# MCU.net
KiCad netlist of a schematic drawn in Altium Designer
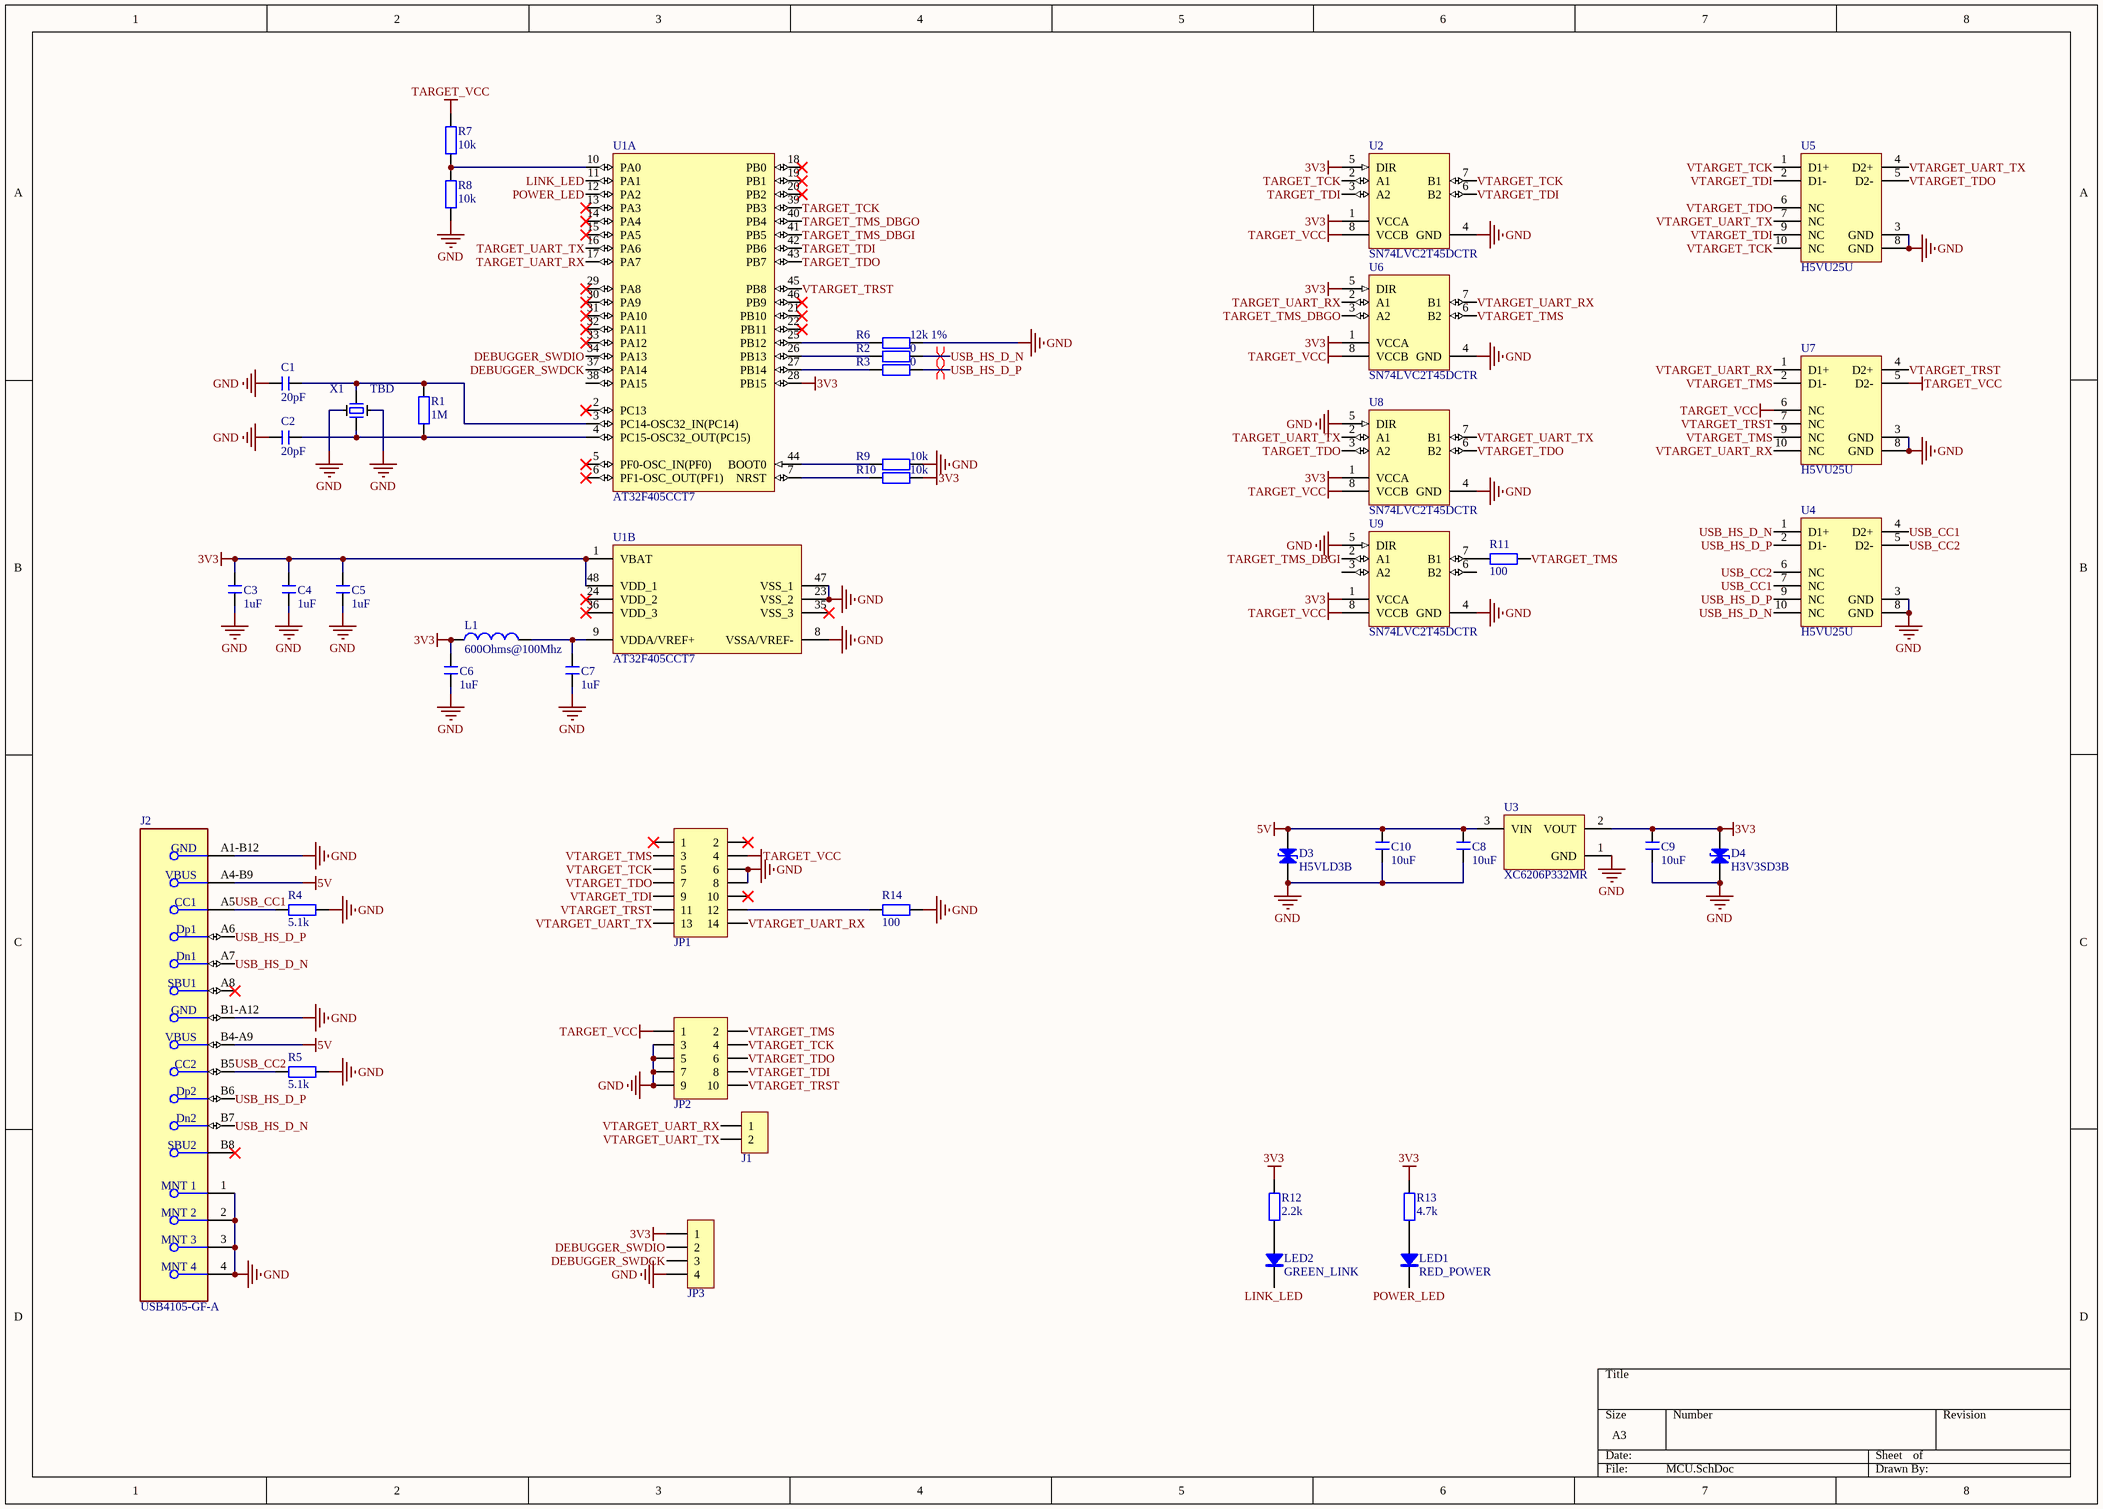
[diagram p0: MCU.SchDoc]

(export (version "E")
  (design (tool "Eeschema 10.0.6"))
  (components
    (comp (ref "C1") (value "20pF") (footprint "C0402") (libsource (lib "Passive") (part "C")))
    (comp (ref "C2") (value "20pF") (footprint "C0402") (libsource (lib "Passive") (part "C")))
    (comp (ref "C3") (value "1uF") (footprint "C0402") (libsource (lib "Passive") (part "C")))
    (comp (ref "C4") (value "1uF") (footprint "C0402") (libsource (lib "Passive") (part "C")))
    (comp (ref "C5") (value "1uF") (footprint "C0402") (libsource (lib "Passive") (part "C")))
    (comp (ref "C6") (value "1uF") (footprint "C0402") (libsource (lib "Passive") (part "C")))
    (comp (ref "C7") (value "1uF") (footprint "C0402") (libsource (lib "Passive") (part "C")))
    (comp (ref "C8") (value "10uF") (footprint "C0603") (libsource (lib "Passive") (part "C")))
    (comp (ref "C9") (value "10uF") (footprint "C0603") (libsource (lib "Passive") (part "C")))
    (comp (ref "C10") (value "10uF") (footprint "C0603") (libsource (lib "Passive") (part "C")))
    (comp (ref "D3")
      (value "H5VLD3B")
      (footprint "SOD-323")
      (description "瞬态电压抑制二极管")
      (fields (field (name "版权归属") "源创客"))
      (libsource (lib "Diode") (part "Generic_BiTVS"))
    )
    (comp (ref "D4")
      (value "H3V3SD3B")
      (footprint "SOD-323")
      (description "瞬态电压抑制二极管")
      (fields (field (name "版权归属") "源创客"))
      (libsource (lib "Diode") (part "Generic_BiTVS"))
    )
    (comp (ref "J1")
      (value "HDR-1X2")
      (footprint "HDR2.54-LI-2P")
      (fields (field (name "版权归属") "源创客"))
      (libsource (lib "Pin2.54") (part "Header 2"))
    )
    (comp (ref "J2")
      (value "USB4105-GF-A")
      (footprint "FP-USB4105-GF-A-MFG")
      (description "CONN RCPT USB2.0 TYPEC 5A")
      (fields
        (field (name "MANUFACTURER") "GCT")
        (field (name "OCTOPART") "https://octopart.com/usb4105-gf-a-gct-106627878")
      )
      (libsource (lib "Altium Content Vault") (part "e7c17a616881a82b79941196b4bec10"))
    )
    (comp (ref "JP1")
      (value "Header 2X7")
      (footprint "HDR1.27-LI-2x7P")
      (description "7*2P接插件")
      (fields (field (name "版权归属") "源创客"))
      (libsource (lib "Pin1.27") (part "Header 7X2"))
    )
    (comp (ref "JP2")
      (value "Header 5X2")
      (footprint "HDR2.54-LI-2x5P")
      (description "5*2P接插件")
      (fields (field (name "版权归属") "源创客"))
      (libsource (lib "Pin2.54") (part "Header 5X2"))
    )
    (comp (ref "JP3")
      (value "HDR-1X4")
      (footprint "HDR2.54-WS-4P")
      (description "4P接插件")
      (fields (field (name "版权归属") "源创客"))
      (libsource (lib "Pin2.54") (part "Header 4"))
    )
    (comp (ref "L1") (value "600Ohms@100Mhz") (footprint "L 0603_L") (libsource (lib "Passive") (part "L")))
    (comp (ref "LED1") (value "RED_POWER") (footprint "LED 0603R") (libsource (lib "Passive") (part "D")))
    (comp (ref "LED2") (value "GREEN_LINK") (footprint "LED 0603G") (libsource (lib "Passive") (part "D")))
    (comp (ref "R1") (value "1M") (footprint "R0402") (libsource (lib "Passive") (part "R")))
    (comp (ref "R2") (value "0") (footprint "R0402") (libsource (lib "Passive") (part "R")))
    (comp (ref "R3") (value "0") (footprint "R0402") (libsource (lib "Passive") (part "R")))
    (comp (ref "R4") (value "5.1k") (footprint "R0402") (libsource (lib "Passive") (part "R")))
    (comp (ref "R5") (value "5.1k") (footprint "R0402") (libsource (lib "Passive") (part "R")))
    (comp (ref "R6") (value "12k 1%") (footprint "R0402") (libsource (lib "Passive") (part "R")))
    (comp (ref "R7") (value "10k") (footprint "R0402") (libsource (lib "Passive") (part "R")))
    (comp (ref "R8") (value "10k") (footprint "R0402") (libsource (lib "Passive") (part "R")))
    (comp (ref "R9") (value "10k") (footprint "R0402") (libsource (lib "Passive") (part "R")))
    (comp (ref "R10") (value "10k") (footprint "R0402") (libsource (lib "Passive") (part "R")))
    (comp (ref "R11") (value "100") (footprint "R0402") (libsource (lib "Passive") (part "R")))
    (comp (ref "R12") (value "2.2k") (footprint "R0402") (libsource (lib "Passive") (part "R")))
    (comp (ref "R13") (value "4.7k") (footprint "R0402") (libsource (lib "Passive") (part "R")))
    (comp (ref "R14") (value "100") (footprint "R0402") (libsource (lib "Passive") (part "R")))
    (comp (ref "U1")
      (value "AT32F405CCT7")
      (footprint "STM-LQFP48_N")
      (fields (field (name "PARTNUMBER") "STM32F303CBT6"))
      (libsource (lib "Altium Content Vault") (part "MC-ARM-STM32F303-SQ48"))
    )
    (comp (ref "U2")
      (value "SN74LVC2T45DCTR")
      (footprint "DCT0008A_N")
      (fields
        (field (name "MANUFACTURER") "Texas Instruments")
        (field (name "GENERIC PART NUMBER") "SN74LVC2T45")
      )
      (libsource (lib "Altium Content Vault") (part "TI-SN74XVC2T45-8"))
    )
    (comp (ref "U3")
      (value "XC6206P332MR")
      (footprint "SOT-23-TT3_N")
      (description "Low Quiescent Current LDO, 3-Pin SOT-23, Extended Temperature, Tape and Reel")
      (libsource (lib "Altium Content Vault") (part "PM-LINEREG-MCP1700-IL3"))
    )
    (comp (ref "U4")
      (value "H5VU25U")
      (footprint "DQA0010A_V")
      (fields (field (name "PARTNUMBER") "TPD4EUSB30DQAR") (field (name "MANUFACTURER") "Texas Instruments"))
      (libsource (lib "Altium Content Vault") (part "TI-TPD4EUSB30-SON_DQA-10"))
    )
    (comp (ref "U5")
      (value "H5VU25U")
      (footprint "DQA0010A_V")
      (fields (field (name "PARTNUMBER") "TPD4EUSB30DQAR") (field (name "MANUFACTURER") "Texas Instruments"))
      (libsource (lib "Altium Content Vault") (part "TI-TPD4EUSB30-SON_DQA-10"))
    )
    (comp (ref "U6")
      (value "SN74LVC2T45DCTR")
      (footprint "DCT0008A_N")
      (fields
        (field (name "MANUFACTURER") "Texas Instruments")
        (field (name "GENERIC PART NUMBER") "SN74LVC2T45")
      )
      (libsource (lib "Altium Content Vault") (part "TI-SN74XVC2T45-8"))
    )
    (comp (ref "U7")
      (value "H5VU25U")
      (footprint "DQA0010A_V")
      (fields (field (name "PARTNUMBER") "TPD4EUSB30DQAR") (field (name "MANUFACTURER") "Texas Instruments"))
      (libsource (lib "Altium Content Vault") (part "TI-TPD4EUSB30-SON_DQA-10"))
    )
    (comp (ref "U8")
      (value "SN74LVC2T45DCTR")
      (footprint "DCT0008A_N")
      (fields
        (field (name "MANUFACTURER") "Texas Instruments")
        (field (name "GENERIC PART NUMBER") "SN74LVC2T45")
      )
      (libsource (lib "Altium Content Vault") (part "TI-SN74XVC2T45-8"))
    )
    (comp (ref "U9")
      (value "SN74LVC2T45DCTR")
      (footprint "DCT0008A_N")
      (fields
        (field (name "MANUFACTURER") "Texas Instruments")
        (field (name "GENERIC PART NUMBER") "SN74LVC2T45")
      )
      (libsource (lib "Altium Content Vault") (part "TI-SN74XVC2T45-8"))
    )
    (comp (ref "X1") (value "TBD") (footprint "3225") (libsource (lib "Passive") (part "X")))
  )
  (nets
    (net (code "1") (name "/DEBUGGER_SWDCK") (class "Default")
      (node (ref "JP3") (pin "3") (pinfunction "3_3") (pintype "passive"))
      (node (ref "U1") (pin "37") (pinfunction "PA14_37") (pintype "bidirectional"))
    )
    (net (code "2") (name "/DEBUGGER_SWDIO") (class "Default")
      (node (ref "JP3") (pin "2") (pinfunction "2_2") (pintype "passive"))
      (node (ref "U1") (pin "34") (pinfunction "PA13_34") (pintype "bidirectional"))
    )
    (net (code "3") (name "/LINK_LED") (class "Default")
      (node (ref "LED2") (pin "2") (pinfunction "K_2") (pintype "passive"))
      (node (ref "U1") (pin "11") (pinfunction "PA1_11") (pintype "bidirectional"))
    )
    (net (code "4") (name "/POWER_LED") (class "Default")
      (node (ref "LED1") (pin "2") (pinfunction "K_2") (pintype "passive"))
      (node (ref "U1") (pin "12") (pinfunction "PA2_12") (pintype "bidirectional"))
    )
    (net (code "5") (name "/TARGET_TCK") (class "Default")
      (node (ref "U1") (pin "39") (pinfunction "PB3_39") (pintype "bidirectional"))
      (node (ref "U2") (pin "2") (pinfunction "A1_2") (pintype "bidirectional"))
    )
    (net (code "6") (name "/TARGET_TDI") (class "Default")
      (node (ref "U1") (pin "42") (pinfunction "PB6_42") (pintype "bidirectional"))
      (node (ref "U2") (pin "3") (pinfunction "A2_3") (pintype "bidirectional"))
    )
    (net (code "7") (name "/TARGET_TDO") (class "Default")
      (node (ref "U1") (pin "43") (pinfunction "PB7_43") (pintype "bidirectional"))
      (node (ref "U8") (pin "3") (pinfunction "A2_3") (pintype "bidirectional"))
    )
    (net (code "8") (name "/TARGET_TMS_DBGI") (class "Default")
      (node (ref "U1") (pin "41") (pinfunction "PB5_41") (pintype "bidirectional"))
      (node (ref "U9") (pin "2") (pinfunction "A1_2") (pintype "bidirectional"))
    )
    (net (code "9") (name "/TARGET_TMS_DBGO") (class "Default")
      (node (ref "U1") (pin "40") (pinfunction "PB4_40") (pintype "bidirectional"))
      (node (ref "U6") (pin "3") (pinfunction "A2_3") (pintype "bidirectional"))
    )
    (net (code "10") (name "/TARGET_UART_RX") (class "Default")
      (node (ref "U1") (pin "17") (pinfunction "PA7_17") (pintype "bidirectional"))
      (node (ref "U6") (pin "2") (pinfunction "A1_2") (pintype "bidirectional"))
    )
    (net (code "11") (name "/TARGET_UART_TX") (class "Default")
      (node (ref "U1") (pin "16") (pinfunction "PA6_16") (pintype "bidirectional"))
      (node (ref "U8") (pin "2") (pinfunction "A1_2") (pintype "bidirectional"))
    )
    (net (code "12") (name "/USB_CC1") (class "Default")
      (node (ref "J2") (pin "A5") (pinfunction "CC1_A5") (pintype "power_in"))
      (node (ref "R4") (pin "2") (pinfunction "2_2") (pintype "passive"))
      (node (ref "U4") (pin "4") (pinfunction "D2+_4") (pintype "passive"))
      (node (ref "U4") (pin "7") (pinfunction "NC_7") (pintype "passive"))
    )
    (net (code "13") (name "/USB_CC2") (class "Default")
      (node (ref "J2") (pin "B5") (pinfunction "CC2_B5") (pintype "bidirectional"))
      (node (ref "R5") (pin "2") (pinfunction "2_2") (pintype "passive"))
      (node (ref "U4") (pin "5") (pinfunction "D2-_5") (pintype "passive"))
      (node (ref "U4") (pin "6") (pinfunction "NC_6") (pintype "passive"))
    )
    (net (code "14") (name "/USB_HS_D_N") (class "Default")
      (node (ref "J2") (pin "A7") (pinfunction "Dn1_A7") (pintype "bidirectional"))
      (node (ref "J2") (pin "B7") (pinfunction "Dn2_B7") (pintype "bidirectional"))
      (node (ref "R2") (pin "1") (pinfunction "1_1") (pintype "passive"))
      (node (ref "U4") (pin "1") (pinfunction "D1+_1") (pintype "passive"))
      (node (ref "U4") (pin "10") (pinfunction "NC_10") (pintype "passive"))
    )
    (net (code "15") (name "/USB_HS_D_P") (class "Default")
      (node (ref "J2") (pin "A6") (pinfunction "Dp1_A6") (pintype "bidirectional"))
      (node (ref "J2") (pin "B6") (pinfunction "Dp2_B6") (pintype "bidirectional"))
      (node (ref "R3") (pin "1") (pinfunction "1_1") (pintype "passive"))
      (node (ref "U4") (pin "2") (pinfunction "D1-_2") (pintype "passive"))
      (node (ref "U4") (pin "9") (pinfunction "NC_9") (pintype "passive"))
    )
    (net (code "16") (name "/VTARGET_TCK") (class "Default")
      (node (ref "JP1") (pin "5") (pinfunction "5_5") (pintype "passive"))
      (node (ref "JP2") (pin "4") (pinfunction "4_4") (pintype "passive"))
      (node (ref "U2") (pin "7") (pinfunction "B1_7") (pintype "bidirectional"))
      (node (ref "U5") (pin "1") (pinfunction "D1+_1") (pintype "passive"))
      (node (ref "U5") (pin "10") (pinfunction "NC_10") (pintype "passive"))
    )
    (net (code "17") (name "/VTARGET_TDI") (class "Default")
      (node (ref "JP1") (pin "9") (pinfunction "9_9") (pintype "passive"))
      (node (ref "JP2") (pin "8") (pinfunction "8_8") (pintype "passive"))
      (node (ref "U2") (pin "6") (pinfunction "B2_6") (pintype "bidirectional"))
      (node (ref "U5") (pin "2") (pinfunction "D1-_2") (pintype "passive"))
      (node (ref "U5") (pin "9") (pinfunction "NC_9") (pintype "passive"))
    )
    (net (code "18") (name "/VTARGET_TDO") (class "Default")
      (node (ref "JP1") (pin "7") (pinfunction "7_7") (pintype "passive"))
      (node (ref "JP2") (pin "6") (pinfunction "6_6") (pintype "passive"))
      (node (ref "U5") (pin "5") (pinfunction "D2-_5") (pintype "passive"))
      (node (ref "U5") (pin "6") (pinfunction "NC_6") (pintype "passive"))
      (node (ref "U8") (pin "6") (pinfunction "B2_6") (pintype "bidirectional"))
    )
    (net (code "19") (name "/VTARGET_TMS") (class "Default")
      (node (ref "JP1") (pin "3") (pinfunction "3_3") (pintype "passive"))
      (node (ref "JP2") (pin "2") (pinfunction "2_2") (pintype "passive"))
      (node (ref "R11") (pin "1") (pinfunction "1_1") (pintype "passive"))
      (node (ref "U6") (pin "6") (pinfunction "B2_6") (pintype "bidirectional"))
      (node (ref "U7") (pin "2") (pinfunction "D1-_2") (pintype "passive"))
      (node (ref "U7") (pin "9") (pinfunction "NC_9") (pintype "passive"))
    )
    (net (code "20") (name "/VTARGET_TRST") (class "Default")
      (node (ref "JP1") (pin "11") (pinfunction "11_11") (pintype "passive"))
      (node (ref "JP2") (pin "10") (pinfunction "10_10") (pintype "passive"))
      (node (ref "U1") (pin "45") (pinfunction "PB8_45") (pintype "bidirectional"))
      (node (ref "U7") (pin "4") (pinfunction "D2+_4") (pintype "passive"))
      (node (ref "U7") (pin "7") (pinfunction "NC_7") (pintype "passive"))
    )
    (net (code "21") (name "/VTARGET_UART_RX") (class "Default")
      (node (ref "J1") (pin "1") (pinfunction "1_1") (pintype "passive"))
      (node (ref "JP1") (pin "14") (pinfunction "14_14") (pintype "passive"))
      (node (ref "U6") (pin "7") (pinfunction "B1_7") (pintype "bidirectional"))
      (node (ref "U7") (pin "1") (pinfunction "D1+_1") (pintype "passive"))
      (node (ref "U7") (pin "10") (pinfunction "NC_10") (pintype "passive"))
    )
    (net (code "22") (name "/VTARGET_UART_TX") (class "Default")
      (node (ref "J1") (pin "2") (pinfunction "2_2") (pintype "passive"))
      (node (ref "JP1") (pin "13") (pinfunction "13_13") (pintype "passive"))
      (node (ref "U5") (pin "4") (pinfunction "D2+_4") (pintype "passive"))
      (node (ref "U5") (pin "7") (pinfunction "NC_7") (pintype "passive"))
      (node (ref "U8") (pin "7") (pinfunction "B1_7") (pintype "bidirectional"))
    )
    (net (code "23") (name "3V3") (class "Default")
      (node (ref "C3") (pin "1") (pinfunction "1_1") (pintype "passive"))
      (node (ref "C4") (pin "1") (pinfunction "1_1") (pintype "passive"))
      (node (ref "C5") (pin "1") (pinfunction "1_1") (pintype "passive"))
      (node (ref "C6") (pin "1") (pinfunction "1_1") (pintype "passive"))
      (node (ref "C9") (pin "1") (pinfunction "1_1") (pintype "passive"))
      (node (ref "D4") (pin "1") (pinfunction "A_1") (pintype "passive"))
      (node (ref "JP3") (pin "1") (pinfunction "1_1") (pintype "passive"))
      (node (ref "L1") (pin "1") (pinfunction "1_1") (pintype "passive"))
      (node (ref "R10") (pin "1") (pinfunction "1_1") (pintype "passive"))
      (node (ref "R12") (pin "1") (pinfunction "1_1") (pintype "passive"))
      (node (ref "R13") (pin "1") (pinfunction "1_1") (pintype "passive"))
      (node (ref "U1") (pin "1") (pinfunction "VBAT_1") (pintype "power_in"))
      (node (ref "U1") (pin "28") (pinfunction "PB15_28") (pintype "bidirectional"))
      (node (ref "U1") (pin "48") (pinfunction "VDD_1_48") (pintype "power_in"))
      (node (ref "U2") (pin "1") (pinfunction "VCCA_1") (pintype "power_in"))
      (node (ref "U2") (pin "5") (pinfunction "DIR_5") (pintype "input"))
      (node (ref "U3") (pin "2") (pinfunction "VOUT_2") (pintype "power_in"))
      (node (ref "U6") (pin "1") (pinfunction "VCCA_1") (pintype "power_in"))
      (node (ref "U6") (pin "5") (pinfunction "DIR_5") (pintype "input"))
      (node (ref "U8") (pin "1") (pinfunction "VCCA_1") (pintype "power_in"))
      (node (ref "U9") (pin "1") (pinfunction "VCCA_1") (pintype "power_in"))
    )
    (net (code "24") (name "5V") (class "Default")
      (node (ref "C10") (pin "1") (pinfunction "1_1") (pintype "passive"))
      (node (ref "C8") (pin "1") (pinfunction "1_1") (pintype "passive"))
      (node (ref "D3") (pin "1") (pinfunction "A_1") (pintype "passive"))
      (node (ref "J2") (pin "A4-B9") (pinfunction "VBUS_A4-B9") (pintype "power_in"))
      (node (ref "J2") (pin "B4-A9") (pinfunction "VBUS_B4-A9") (pintype "bidirectional"))
      (node (ref "U3") (pin "3") (pinfunction "VIN_3") (pintype "power_in"))
    )
    (net (code "25") (name "GND") (class "Default")
      (node (ref "C1") (pin "2") (pinfunction "2_2") (pintype "passive"))
      (node (ref "C10") (pin "2") (pinfunction "2_2") (pintype "passive"))
      (node (ref "C2") (pin "2") (pinfunction "2_2") (pintype "passive"))
      (node (ref "C3") (pin "2") (pinfunction "2_2") (pintype "passive"))
      (node (ref "C4") (pin "2") (pinfunction "2_2") (pintype "passive"))
      (node (ref "C5") (pin "2") (pinfunction "2_2") (pintype "passive"))
      (node (ref "C6") (pin "2") (pinfunction "2_2") (pintype "passive"))
      (node (ref "C7") (pin "2") (pinfunction "2_2") (pintype "passive"))
      (node (ref "C8") (pin "2") (pinfunction "2_2") (pintype "passive"))
      (node (ref "C9") (pin "2") (pinfunction "2_2") (pintype "passive"))
      (node (ref "D3") (pin "2") (pinfunction "K_2") (pintype "passive"))
      (node (ref "D4") (pin "2") (pinfunction "K_2") (pintype "passive"))
      (node (ref "J2") (pin "1") (pinfunction "MNT_1_1") (pintype "power_in"))
      (node (ref "J2") (pin "2") (pinfunction "MNT_2_2") (pintype "power_in"))
      (node (ref "J2") (pin "3") (pinfunction "MNT_3_3") (pintype "power_in"))
      (node (ref "J2") (pin "4") (pinfunction "MNT_4_4") (pintype "power_in"))
      (node (ref "J2") (pin "A1-B12") (pinfunction "GND_A1-B12") (pintype "power_in"))
      (node (ref "J2") (pin "B1-A12") (pinfunction "GND_B1-A12") (pintype "bidirectional"))
      (node (ref "JP1") (pin "6") (pinfunction "6_6") (pintype "passive"))
      (node (ref "JP1") (pin "8") (pinfunction "8_8") (pintype "passive"))
      (node (ref "JP2") (pin "3") (pinfunction "3_3") (pintype "passive"))
      (node (ref "JP2") (pin "5") (pinfunction "5_5") (pintype "passive"))
      (node (ref "JP2") (pin "7") (pinfunction "7_7") (pintype "passive"))
      (node (ref "JP2") (pin "9") (pinfunction "9_9") (pintype "passive"))
      (node (ref "JP3") (pin "4") (pinfunction "4_4") (pintype "passive"))
      (node (ref "R14") (pin "1") (pinfunction "1_1") (pintype "passive"))
      (node (ref "R4") (pin "1") (pinfunction "1_1") (pintype "passive"))
      (node (ref "R5") (pin "1") (pinfunction "1_1") (pintype "passive"))
      (node (ref "R6") (pin "1") (pinfunction "1_1") (pintype "passive"))
      (node (ref "R8") (pin "1") (pinfunction "1_1") (pintype "passive"))
      (node (ref "R9") (pin "1") (pinfunction "1_1") (pintype "passive"))
      (node (ref "U1") (pin "23") (pinfunction "VSS_2_23") (pintype "power_in"))
      (node (ref "U1") (pin "47") (pinfunction "VSS_1_47") (pintype "power_in"))
      (node (ref "U1") (pin "8") (pinfunction "VSSA/VREF-_8") (pintype "power_in"))
      (node (ref "U2") (pin "4") (pinfunction "GND_4") (pintype "power_in"))
      (node (ref "U3") (pin "1") (pinfunction "GND_1") (pintype "power_in"))
      (node (ref "U4") (pin "3") (pinfunction "GND_3") (pintype "power_in"))
      (node (ref "U4") (pin "8") (pinfunction "GND_8") (pintype "power_in"))
      (node (ref "U5") (pin "3") (pinfunction "GND_3") (pintype "power_in"))
      (node (ref "U5") (pin "8") (pinfunction "GND_8") (pintype "power_in"))
      (node (ref "U6") (pin "4") (pinfunction "GND_4") (pintype "power_in"))
      (node (ref "U7") (pin "3") (pinfunction "GND_3") (pintype "power_in"))
      (node (ref "U7") (pin "8") (pinfunction "GND_8") (pintype "power_in"))
      (node (ref "U8") (pin "4") (pinfunction "GND_4") (pintype "power_in"))
      (node (ref "U8") (pin "5") (pinfunction "DIR_5") (pintype "input"))
      (node (ref "U9") (pin "4") (pinfunction "GND_4") (pintype "power_in"))
      (node (ref "U9") (pin "5") (pinfunction "DIR_5") (pintype "input"))
      (node (ref "X1") (pin "2") (pinfunction "2_2") (pintype "passive"))
      (node (ref "X1") (pin "4") (pinfunction "2_4") (pintype "passive"))
    )
    (net (code "26") (name "Net-(JP1-Pad12)") (class "Default")
      (node (ref "JP1") (pin "12") (pinfunction "12_12") (pintype "passive"))
      (node (ref "R14") (pin "2") (pinfunction "2_2") (pintype "passive"))
    )
    (net (code "27") (name "Net-(LED1-A)") (class "Default")
      (node (ref "LED1") (pin "1") (pinfunction "A_1") (pintype "passive"))
      (node (ref "R13") (pin "2") (pinfunction "2_2") (pintype "passive"))
    )
    (net (code "28") (name "Net-(LED2-A)") (class "Default")
      (node (ref "LED2") (pin "1") (pinfunction "A_1") (pintype "passive"))
      (node (ref "R12") (pin "2") (pinfunction "2_2") (pintype "passive"))
    )
    (net (code "29") (name "Net-(U1A-BOOT0)") (class "Default")
      (node (ref "R9") (pin "2") (pinfunction "2_2") (pintype "passive"))
      (node (ref "U1") (pin "44") (pinfunction "BOOT0_44") (pintype "input"))
    )
    (net (code "30") (name "Net-(U1A-NRST)") (class "Default")
      (node (ref "R10") (pin "2") (pinfunction "2_2") (pintype "passive"))
      (node (ref "U1") (pin "7") (pinfunction "NRST_7") (pintype "bidirectional"))
    )
    (net (code "31") (name "Net-(U1A-PA0)") (class "Default")
      (node (ref "R7") (pin "1") (pinfunction "1_1") (pintype "passive"))
      (node (ref "R8") (pin "2") (pinfunction "2_2") (pintype "passive"))
      (node (ref "U1") (pin "10") (pinfunction "PA0_10") (pintype "bidirectional"))
    )
    (net (code "32") (name "Net-(U1A-PB12)") (class "Default")
      (node (ref "R6") (pin "2") (pinfunction "2_2") (pintype "passive"))
      (node (ref "U1") (pin "25") (pinfunction "PB12_25") (pintype "bidirectional"))
    )
    (net (code "33") (name "Net-(U1A-PB13)") (class "Default")
      (node (ref "R2") (pin "2") (pinfunction "2_2") (pintype "passive"))
      (node (ref "U1") (pin "26") (pinfunction "PB13_26") (pintype "bidirectional"))
    )
    (net (code "34") (name "Net-(U1A-PB14)") (class "Default")
      (node (ref "R3") (pin "2") (pinfunction "2_2") (pintype "passive"))
      (node (ref "U1") (pin "27") (pinfunction "PB14_27") (pintype "bidirectional"))
    )
    (net (code "35") (name "Net-(U1A-PC14-OSC32_IN(PC14))") (class "Default")
      (node (ref "C1") (pin "1") (pinfunction "1_1") (pintype "passive"))
      (node (ref "R1") (pin "2") (pinfunction "2_2") (pintype "passive"))
      (node (ref "U1") (pin "3") (pinfunction "PC14-OSC32_IN(PC14)_3") (pintype "bidirectional"))
      (node (ref "X1") (pin "3") (pinfunction "2_3") (pintype "passive"))
    )
    (net (code "36") (name "Net-(U1A-PC15-OSC32_OUT(PC15))") (class "Default")
      (node (ref "C2") (pin "1") (pinfunction "1_1") (pintype "passive"))
      (node (ref "R1") (pin "1") (pinfunction "1_1") (pintype "passive"))
      (node (ref "U1") (pin "4") (pinfunction "PC15-OSC32_OUT(PC15)_4") (pintype "bidirectional"))
      (node (ref "X1") (pin "1") (pinfunction "1_1") (pintype "passive"))
    )
    (net (code "37") (name "Net-(U1B-VDDA{slash}VREF+)") (class "Default")
      (node (ref "C7") (pin "1") (pinfunction "1_1") (pintype "passive"))
      (node (ref "L1") (pin "2") (pinfunction "2_2") (pintype "passive"))
      (node (ref "U1") (pin "9") (pinfunction "VDDA/VREF+_9") (pintype "power_in"))
    )
    (net (code "38") (name "Net-(U9-B1)") (class "Default")
      (node (ref "R11") (pin "2") (pinfunction "2_2") (pintype "passive"))
      (node (ref "U9") (pin "7") (pinfunction "B1_7") (pintype "bidirectional"))
    )
    (net (code "39") (name "TARGET_VCC") (class "Default")
      (node (ref "JP1") (pin "4") (pinfunction "4_4") (pintype "passive"))
      (node (ref "JP2") (pin "1") (pinfunction "1_1") (pintype "passive"))
      (node (ref "R7") (pin "2") (pinfunction "2_2") (pintype "passive"))
      (node (ref "U2") (pin "8") (pinfunction "VCCB_8") (pintype "power_in"))
      (node (ref "U6") (pin "8") (pinfunction "VCCB_8") (pintype "power_in"))
      (node (ref "U7") (pin "5") (pinfunction "D2-_5") (pintype "passive"))
      (node (ref "U7") (pin "6") (pinfunction "NC_6") (pintype "passive"))
      (node (ref "U8") (pin "8") (pinfunction "VCCB_8") (pintype "power_in"))
      (node (ref "U9") (pin "8") (pinfunction "VCCB_8") (pintype "power_in"))
    )
    (net (code "40") (name "unconnected-(J2-SBU1-PadA8)") (class "Default")
      (node (ref "J2") (pin "A8") (pinfunction "SBU1_A8") (pintype "bidirectional+no_connect"))
    )
    (net (code "41") (name "unconnected-(J2-SBU2-PadB8)") (class "Default")
      (node (ref "J2") (pin "B8") (pinfunction "SBU2_B8") (pintype "power_in+no_connect"))
    )
    (net (code "42") (name "unconnected-(JP1-Pad1)") (class "Default")
      (node (ref "JP1") (pin "1") (pinfunction "1_1") (pintype "passive+no_connect"))
    )
    (net (code "43") (name "unconnected-(JP1-Pad2)") (class "Default")
      (node (ref "JP1") (pin "2") (pinfunction "2_2") (pintype "passive+no_connect"))
    )
    (net (code "44") (name "unconnected-(JP1-Pad10)") (class "Default")
      (node (ref "JP1") (pin "10") (pinfunction "10_10") (pintype "passive+no_connect"))
    )
    (net (code "45") (name "unconnected-(U1A-PA3-Pad13)") (class "Default")
      (node (ref "U1") (pin "13") (pinfunction "PA3_13") (pintype "bidirectional+no_connect"))
    )
    (net (code "46") (name "unconnected-(U1A-PA4-Pad14)") (class "Default")
      (node (ref "U1") (pin "14") (pinfunction "PA4_14") (pintype "bidirectional+no_connect"))
    )
    (net (code "47") (name "unconnected-(U1A-PA5-Pad15)") (class "Default")
      (node (ref "U1") (pin "15") (pinfunction "PA5_15") (pintype "bidirectional+no_connect"))
    )
    (net (code "48") (name "unconnected-(U1A-PA8-Pad29)") (class "Default")
      (node (ref "U1") (pin "29") (pinfunction "PA8_29") (pintype "bidirectional+no_connect"))
    )
    (net (code "49") (name "unconnected-(U1A-PA9-Pad30)") (class "Default")
      (node (ref "U1") (pin "30") (pinfunction "PA9_30") (pintype "bidirectional+no_connect"))
    )
    (net (code "50") (name "unconnected-(U1A-PA10-Pad31)") (class "Default")
      (node (ref "U1") (pin "31") (pinfunction "PA10_31") (pintype "bidirectional+no_connect"))
    )
    (net (code "51") (name "unconnected-(U1A-PA11-Pad32)") (class "Default")
      (node (ref "U1") (pin "32") (pinfunction "PA11_32") (pintype "bidirectional+no_connect"))
    )
    (net (code "52") (name "unconnected-(U1A-PA12-Pad33)") (class "Default")
      (node (ref "U1") (pin "33") (pinfunction "PA12_33") (pintype "bidirectional+no_connect"))
    )
    (net (code "53") (name "unconnected-(U1A-PA15-Pad38)") (class "Default")
      (node (ref "U1") (pin "38") (pinfunction "PA15_38") (pintype "bidirectional"))
    )
    (net (code "54") (name "unconnected-(U1A-PB0-Pad18)") (class "Default")
      (node (ref "U1") (pin "18") (pinfunction "PB0_18") (pintype "bidirectional+no_connect"))
    )
    (net (code "55") (name "unconnected-(U1A-PB1-Pad19)") (class "Default")
      (node (ref "U1") (pin "19") (pinfunction "PB1_19") (pintype "bidirectional+no_connect"))
    )
    (net (code "56") (name "unconnected-(U1A-PB2-Pad20)") (class "Default")
      (node (ref "U1") (pin "20") (pinfunction "PB2_20") (pintype "bidirectional+no_connect"))
    )
    (net (code "57") (name "unconnected-(U1A-PB9-Pad46)") (class "Default")
      (node (ref "U1") (pin "46") (pinfunction "PB9_46") (pintype "bidirectional+no_connect"))
    )
    (net (code "58") (name "unconnected-(U1A-PB10-Pad21)") (class "Default")
      (node (ref "U1") (pin "21") (pinfunction "PB10_21") (pintype "bidirectional+no_connect"))
    )
    (net (code "59") (name "unconnected-(U1A-PB11-Pad22)") (class "Default")
      (node (ref "U1") (pin "22") (pinfunction "PB11_22") (pintype "bidirectional+no_connect"))
    )
    (net (code "60") (name "unconnected-(U1A-PC13-Pad2)") (class "Default")
      (node (ref "U1") (pin "2") (pinfunction "PC13_2") (pintype "bidirectional+no_connect"))
    )
    (net (code "61") (name "unconnected-(U1A-PF0-OSC_IN(PF0)-Pad5)") (class "Default")
      (node (ref "U1") (pin "5") (pinfunction "PF0-OSC_IN(PF0)_5") (pintype "bidirectional+no_connect"))
    )
    (net (code "62") (name "unconnected-(U1A-PF1-OSC_OUT(PF1)-Pad6)") (class "Default")
      (node (ref "U1") (pin "6") (pinfunction "PF1-OSC_OUT(PF1)_6") (pintype "bidirectional+no_connect"))
    )
    (net (code "63") (name "unconnected-(U1B-VDD_2-Pad24)") (class "Default")
      (node (ref "U1") (pin "24") (pinfunction "VDD_2_24") (pintype "power_in+no_connect"))
    )
    (net (code "64") (name "unconnected-(U1B-VDD_3-Pad36)") (class "Default")
      (node (ref "U1") (pin "36") (pinfunction "VDD_3_36") (pintype "power_in+no_connect"))
    )
    (net (code "65") (name "unconnected-(U1B-VSS_3-Pad35)") (class "Default")
      (node (ref "U1") (pin "35") (pinfunction "VSS_3_35") (pintype "power_in+no_connect"))
    )
    (net (code "66") (name "unconnected-(U9-A2-Pad3)") (class "Default")
      (node (ref "U9") (pin "3") (pinfunction "A2_3") (pintype "bidirectional"))
    )
    (net (code "67") (name "unconnected-(U9-B2-Pad6)") (class "Default")
      (node (ref "U9") (pin "6") (pinfunction "B2_6") (pintype "bidirectional"))
    )
  )
)
